# Ring_2_B.net
KiCad netlist of a schematic drawn in Altium Designer
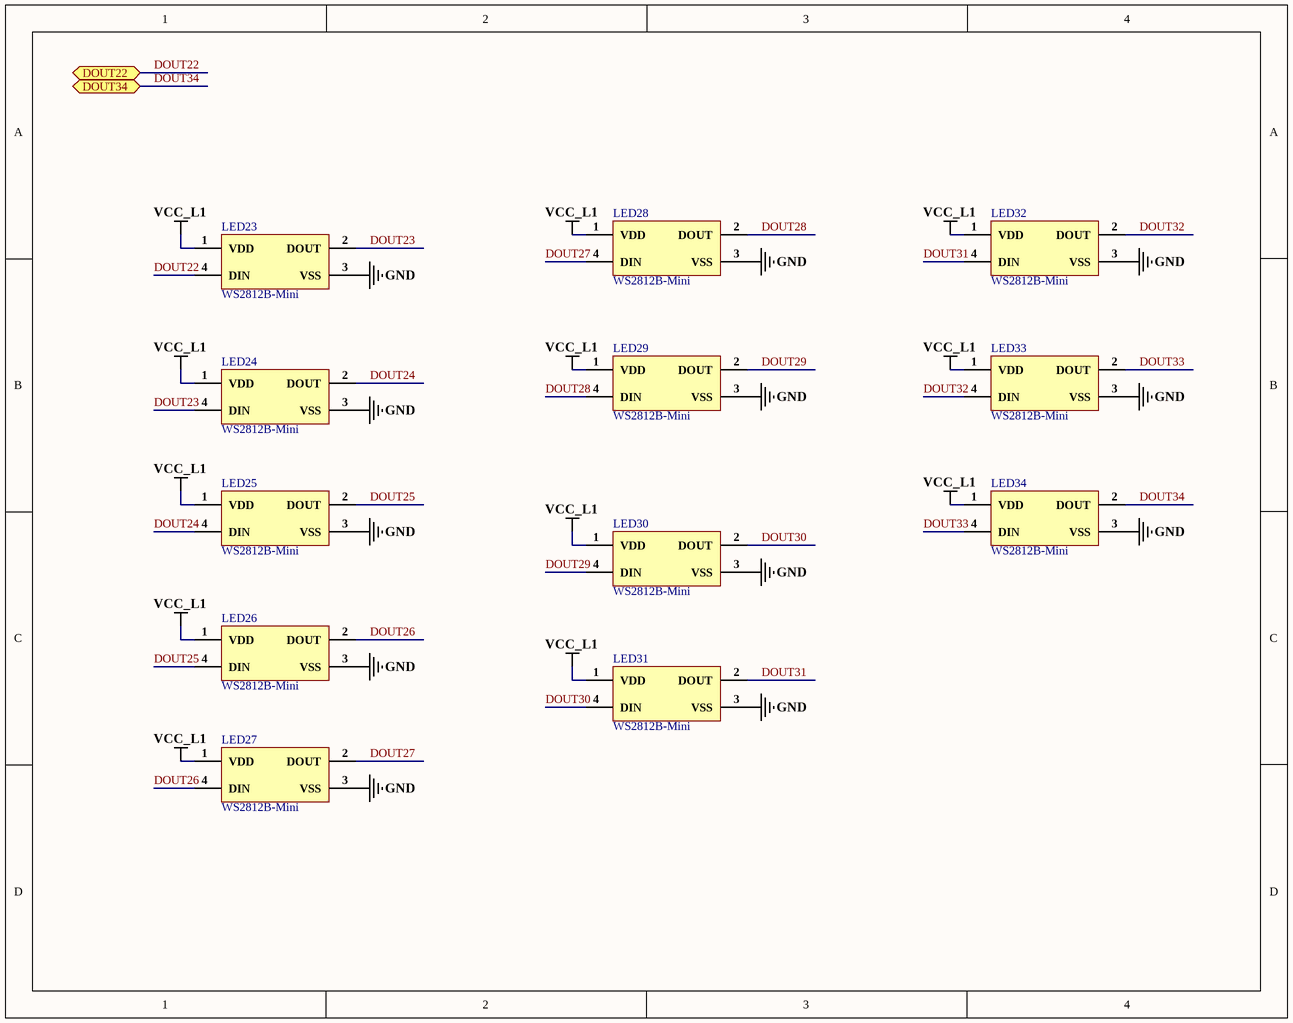
[diagram p0: Ring 2_B.SchDoc]

(export (version "E")
  (design (tool "Eeschema 10.0.6"))
  (components
    (comp (ref "LED23")
      (value "WS2812B-Mini")
      (footprint "WS2812B-Mini")
      (description "SMD,3.5x3.5mm Light Emitting Diodes (LED) RoHS")
      (fields (field (name "MANUFACTURER") "Worldsemi"))
      (libsource (lib "TT_IntLib") (part "WS2812B-Mini"))
    )
    (comp (ref "LED24")
      (value "WS2812B-Mini")
      (footprint "WS2812B-Mini")
      (description "SMD,3.5x3.5mm Light Emitting Diodes (LED) RoHS")
      (fields (field (name "MANUFACTURER") "Worldsemi"))
      (libsource (lib "TT_IntLib") (part "WS2812B-Mini"))
    )
    (comp (ref "LED25")
      (value "WS2812B-Mini")
      (footprint "WS2812B-Mini")
      (description "SMD,3.5x3.5mm Light Emitting Diodes (LED) RoHS")
      (fields (field (name "MANUFACTURER") "Worldsemi"))
      (libsource (lib "TT_IntLib") (part "WS2812B-Mini"))
    )
    (comp (ref "LED26")
      (value "WS2812B-Mini")
      (footprint "WS2812B-Mini")
      (description "SMD,3.5x3.5mm Light Emitting Diodes (LED) RoHS")
      (fields (field (name "MANUFACTURER") "Worldsemi"))
      (libsource (lib "TT_IntLib") (part "WS2812B-Mini"))
    )
    (comp (ref "LED27")
      (value "WS2812B-Mini")
      (footprint "WS2812B-Mini")
      (description "SMD,3.5x3.5mm Light Emitting Diodes (LED) RoHS")
      (fields (field (name "MANUFACTURER") "Worldsemi"))
      (libsource (lib "TT_IntLib") (part "WS2812B-Mini"))
    )
    (comp (ref "LED28")
      (value "WS2812B-Mini")
      (footprint "WS2812B-Mini")
      (description "SMD,3.5x3.5mm Light Emitting Diodes (LED) RoHS")
      (fields (field (name "MANUFACTURER") "Worldsemi"))
      (libsource (lib "TT_IntLib") (part "WS2812B-Mini"))
    )
    (comp (ref "LED29")
      (value "WS2812B-Mini")
      (footprint "WS2812B-Mini")
      (description "SMD,3.5x3.5mm Light Emitting Diodes (LED) RoHS")
      (fields (field (name "MANUFACTURER") "Worldsemi"))
      (libsource (lib "TT_IntLib") (part "WS2812B-Mini"))
    )
    (comp (ref "LED30")
      (value "WS2812B-Mini")
      (footprint "WS2812B-Mini")
      (description "SMD,3.5x3.5mm Light Emitting Diodes (LED) RoHS")
      (fields (field (name "MANUFACTURER") "Worldsemi"))
      (libsource (lib "TT_IntLib") (part "WS2812B-Mini"))
    )
    (comp (ref "LED31")
      (value "WS2812B-Mini")
      (footprint "WS2812B-Mini")
      (description "SMD,3.5x3.5mm Light Emitting Diodes (LED) RoHS")
      (fields (field (name "MANUFACTURER") "Worldsemi"))
      (libsource (lib "TT_IntLib") (part "WS2812B-Mini"))
    )
    (comp (ref "LED32")
      (value "WS2812B-Mini")
      (footprint "WS2812B-Mini")
      (description "SMD,3.5x3.5mm Light Emitting Diodes (LED) RoHS")
      (fields (field (name "MANUFACTURER") "Worldsemi"))
      (libsource (lib "TT_IntLib") (part "WS2812B-Mini"))
    )
    (comp (ref "LED33")
      (value "WS2812B-Mini")
      (footprint "WS2812B-Mini")
      (description "SMD,3.5x3.5mm Light Emitting Diodes (LED) RoHS")
      (fields (field (name "MANUFACTURER") "Worldsemi"))
      (libsource (lib "TT_IntLib") (part "WS2812B-Mini"))
    )
    (comp (ref "LED34")
      (value "WS2812B-Mini")
      (footprint "WS2812B-Mini")
      (description "SMD,3.5x3.5mm Light Emitting Diodes (LED) RoHS")
      (fields (field (name "MANUFACTURER") "Worldsemi"))
      (libsource (lib "TT_IntLib") (part "WS2812B-Mini"))
    )
  )
  (nets
    (net (code "1") (name "/DOUT22") (class "Default")
      (node (ref "LED23") (pin "4") (pinfunction "DIN_4") (pintype "passive"))
    )
    (net (code "2") (name "/DOUT23") (class "Default")
      (node (ref "LED23") (pin "2") (pinfunction "DOUT_2") (pintype "passive"))
      (node (ref "LED24") (pin "4") (pinfunction "DIN_4") (pintype "passive"))
    )
    (net (code "3") (name "/DOUT24") (class "Default")
      (node (ref "LED24") (pin "2") (pinfunction "DOUT_2") (pintype "passive"))
      (node (ref "LED25") (pin "4") (pinfunction "DIN_4") (pintype "passive"))
    )
    (net (code "4") (name "/DOUT25") (class "Default")
      (node (ref "LED25") (pin "2") (pinfunction "DOUT_2") (pintype "passive"))
      (node (ref "LED26") (pin "4") (pinfunction "DIN_4") (pintype "passive"))
    )
    (net (code "5") (name "/DOUT26") (class "Default")
      (node (ref "LED26") (pin "2") (pinfunction "DOUT_2") (pintype "passive"))
      (node (ref "LED27") (pin "4") (pinfunction "DIN_4") (pintype "passive"))
    )
    (net (code "6") (name "/DOUT27") (class "Default")
      (node (ref "LED27") (pin "2") (pinfunction "DOUT_2") (pintype "passive"))
      (node (ref "LED28") (pin "4") (pinfunction "DIN_4") (pintype "passive"))
    )
    (net (code "7") (name "/DOUT28") (class "Default")
      (node (ref "LED28") (pin "2") (pinfunction "DOUT_2") (pintype "passive"))
      (node (ref "LED29") (pin "4") (pinfunction "DIN_4") (pintype "passive"))
    )
    (net (code "8") (name "/DOUT29") (class "Default")
      (node (ref "LED29") (pin "2") (pinfunction "DOUT_2") (pintype "passive"))
      (node (ref "LED30") (pin "4") (pinfunction "DIN_4") (pintype "passive"))
    )
    (net (code "9") (name "/DOUT30") (class "Default")
      (node (ref "LED30") (pin "2") (pinfunction "DOUT_2") (pintype "passive"))
      (node (ref "LED31") (pin "4") (pinfunction "DIN_4") (pintype "passive"))
    )
    (net (code "10") (name "/DOUT31") (class "Default")
      (node (ref "LED31") (pin "2") (pinfunction "DOUT_2") (pintype "passive"))
      (node (ref "LED32") (pin "4") (pinfunction "DIN_4") (pintype "passive"))
    )
    (net (code "11") (name "/DOUT32") (class "Default")
      (node (ref "LED32") (pin "2") (pinfunction "DOUT_2") (pintype "passive"))
      (node (ref "LED33") (pin "4") (pinfunction "DIN_4") (pintype "passive"))
    )
    (net (code "12") (name "/DOUT33") (class "Default")
      (node (ref "LED33") (pin "2") (pinfunction "DOUT_2") (pintype "passive"))
      (node (ref "LED34") (pin "4") (pinfunction "DIN_4") (pintype "passive"))
    )
    (net (code "13") (name "/DOUT34") (class "Default")
      (node (ref "LED34") (pin "2") (pinfunction "DOUT_2") (pintype "passive"))
    )
    (net (code "14") (name "GND") (class "Default")
      (node (ref "LED23") (pin "3") (pinfunction "VSS_3") (pintype "passive"))
      (node (ref "LED24") (pin "3") (pinfunction "VSS_3") (pintype "passive"))
      (node (ref "LED25") (pin "3") (pinfunction "VSS_3") (pintype "passive"))
      (node (ref "LED26") (pin "3") (pinfunction "VSS_3") (pintype "passive"))
      (node (ref "LED27") (pin "3") (pinfunction "VSS_3") (pintype "passive"))
      (node (ref "LED28") (pin "3") (pinfunction "VSS_3") (pintype "passive"))
      (node (ref "LED29") (pin "3") (pinfunction "VSS_3") (pintype "passive"))
      (node (ref "LED30") (pin "3") (pinfunction "VSS_3") (pintype "passive"))
      (node (ref "LED31") (pin "3") (pinfunction "VSS_3") (pintype "passive"))
      (node (ref "LED32") (pin "3") (pinfunction "VSS_3") (pintype "passive"))
      (node (ref "LED33") (pin "3") (pinfunction "VSS_3") (pintype "passive"))
      (node (ref "LED34") (pin "3") (pinfunction "VSS_3") (pintype "passive"))
    )
    (net (code "15") (name "VCC_L1") (class "Default")
      (node (ref "LED23") (pin "1") (pinfunction "VDD_1") (pintype "passive"))
      (node (ref "LED24") (pin "1") (pinfunction "VDD_1") (pintype "passive"))
      (node (ref "LED25") (pin "1") (pinfunction "VDD_1") (pintype "passive"))
      (node (ref "LED26") (pin "1") (pinfunction "VDD_1") (pintype "passive"))
      (node (ref "LED27") (pin "1") (pinfunction "VDD_1") (pintype "passive"))
      (node (ref "LED28") (pin "1") (pinfunction "VDD_1") (pintype "passive"))
      (node (ref "LED29") (pin "1") (pinfunction "VDD_1") (pintype "passive"))
      (node (ref "LED30") (pin "1") (pinfunction "VDD_1") (pintype "passive"))
      (node (ref "LED31") (pin "1") (pinfunction "VDD_1") (pintype "passive"))
      (node (ref "LED32") (pin "1") (pinfunction "VDD_1") (pintype "passive"))
      (node (ref "LED33") (pin "1") (pinfunction "VDD_1") (pintype "passive"))
      (node (ref "LED34") (pin "1") (pinfunction "VDD_1") (pintype "passive"))
    )
  )
)
